# StLink.net
KiCad netlist of a schematic drawn in Altium Designer
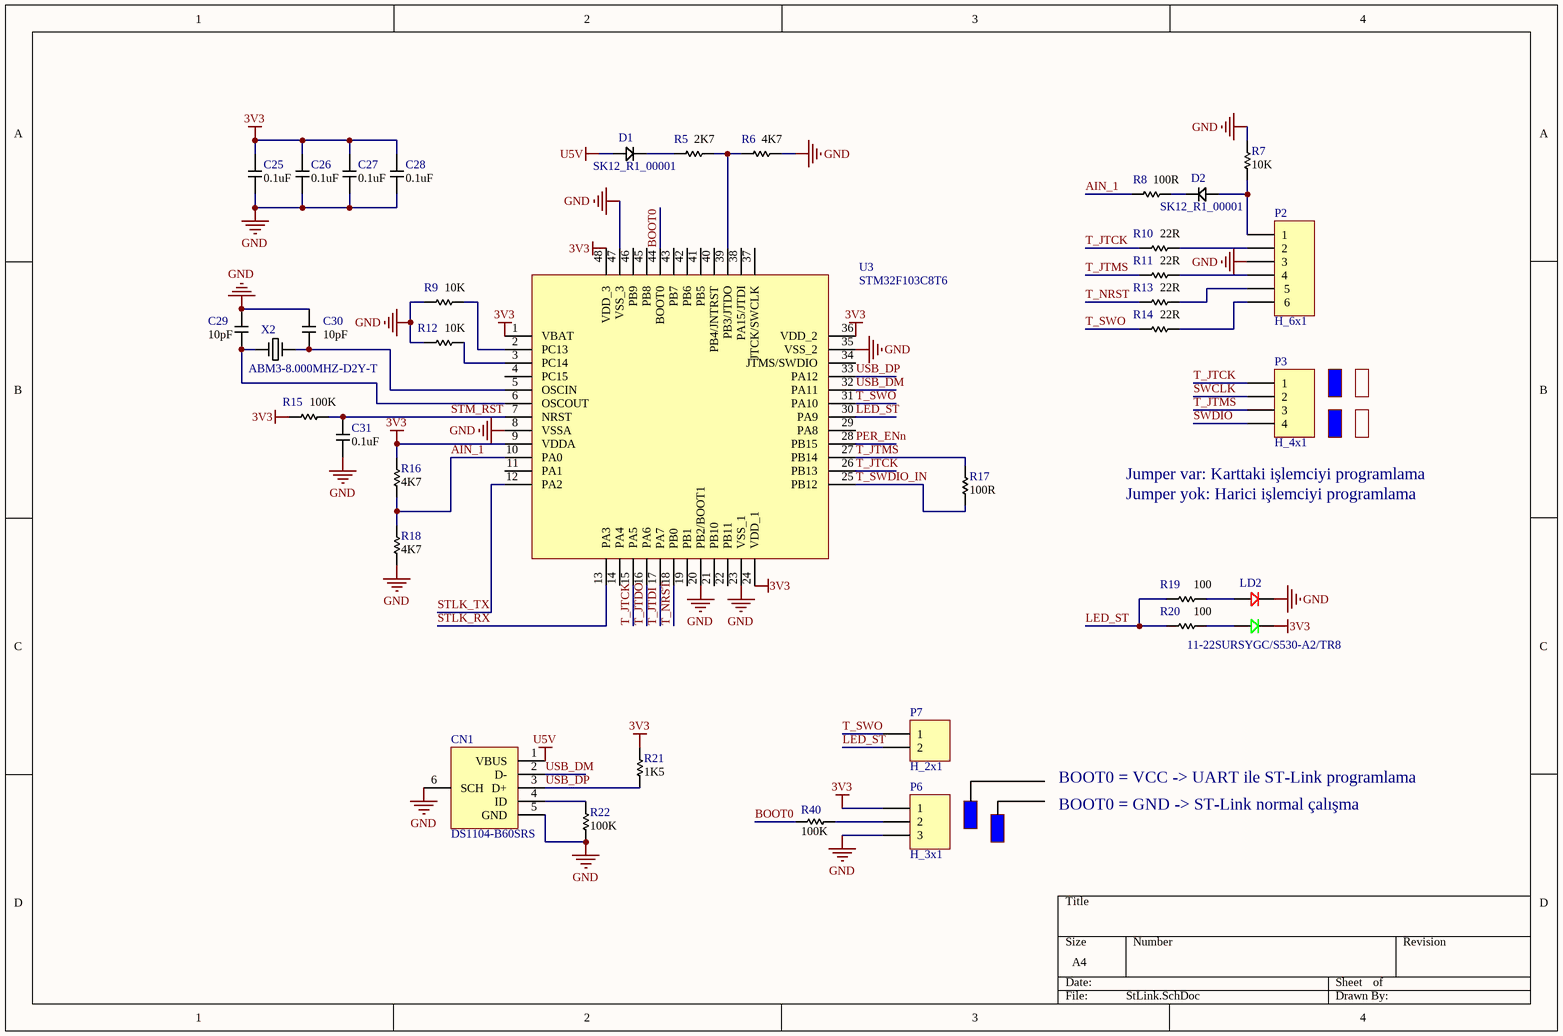
[diagram p0: StLink.SchDoc]

(export (version "E")
  (design (tool "Eeschema 10.0.6"))
  (components
    (comp (ref "C25")
      (value "0.1uF")
      (footprint "Kemet_0805_X7R")
      (description "Cap_0805_0.1uF_25VDC_Kemet")
      (fields (field (name "MANUFACTURER") "Kemet") (field (name "VOLTAGE") "25VDC"))
      (libsource (lib "Capacitor") (part "C0805C104K3RACTU"))
    )
    (comp (ref "C26")
      (value "0.1uF")
      (footprint "Kemet_0805_X7R")
      (description "Cap_0805_0.1uF_25VDC_Kemet")
      (fields (field (name "MANUFACTURER") "Kemet") (field (name "VOLTAGE") "25VDC"))
      (libsource (lib "Capacitor") (part "C0805C104K3RACTU"))
    )
    (comp (ref "C27")
      (value "0.1uF")
      (footprint "Kemet_0805_X7R")
      (description "Cap_0805_0.1uF_25VDC_Kemet")
      (fields (field (name "MANUFACTURER") "Kemet") (field (name "VOLTAGE") "25VDC"))
      (libsource (lib "Capacitor") (part "C0805C104K3RACTU"))
    )
    (comp (ref "C28")
      (value "0.1uF")
      (footprint "Kemet_0805_X7R")
      (description "Cap_0805_0.1uF_25VDC_Kemet")
      (fields (field (name "MANUFACTURER") "Kemet") (field (name "VOLTAGE") "25VDC"))
      (libsource (lib "Capacitor") (part "C0805C104K3RACTU"))
    )
    (comp (ref "C29")
      (value "10pF")
      (footprint "Kemet_0805_X7R")
      (description "Cap_0805_0.1uF_25VDC_Kemet")
      (fields (field (name "MANUFACTURER") "Kemet") (field (name "VOLTAGE") "25VDC"))
      (libsource (lib "Capacitor") (part "C0805C104K3RACTU"))
    )
    (comp (ref "C30")
      (value "10pF")
      (footprint "Kemet_0805_X7R")
      (description "Cap_0805_0.1uF_25VDC_Kemet")
      (fields (field (name "MANUFACTURER") "Kemet") (field (name "VOLTAGE") "25VDC"))
      (libsource (lib "Capacitor") (part "C0805C104K3RACTU"))
    )
    (comp (ref "C31")
      (value "0.1uF")
      (footprint "Kemet_0805_X7R")
      (description "Cap_0805_0.1uF_25VDC_Kemet")
      (fields (field (name "MANUFACTURER") "Kemet") (field (name "VOLTAGE") "25VDC"))
      (libsource (lib "Capacitor") (part "C0805C104K3RACTU"))
    )
    (comp (ref "CN1")
      (value "DS1104-B60SRS")
      (footprint "Connfly_DS1104-B60SRS")
      (description "UsbConn_Mini_5Pin_SMT_Connfly")
      (libsource (lib "UsbConnecttor") (part "DS1104-B60SRS"))
    )
    (comp (ref "D1")
      (value "SK12_R1_00001")
      (footprint "Panjit_DO214AA_2")
      (description "Schottky_1A_0.6V_20V_Panjit")
      (fields (field (name "MANUFACTURER") "Panjit"))
      (libsource (lib "Diode") (part "SK12_R1_00001"))
    )
    (comp (ref "D2")
      (value "SK12_R1_00001")
      (footprint "Panjit_DO214AA_2")
      (description "Schottky_1A_0.6V_20V_Panjit")
      (fields (field (name "MANUFACTURER") "Panjit"))
      (libsource (lib "Diode") (part "SK12_R1_00001"))
    )
    (comp (ref "LD2")
      (value "11-22SURSYGC/S530-A2/TR8")
      (footprint "Everlight_11-22SURSYGC")
      (description "Led_RG_1.7-2.4V_25mA_Everlight")
      (fields (field (name "MANUFACTURER") "Everlight"))
      (libsource (lib "LED") (part "11-22SURSYGC/S530-A2/TR8"))
    )
    (comp (ref "P2")
      (value "H_6x1")
      (footprint "HEADER_HDRV6W65P254_6X1_1524X254H945")
      (description "Head_6x1_2.54")
      (libsource (lib "Header") (part "H_6x1"))
    )
    (comp (ref "P3")
      (value "H_4x1")
      (footprint "HEADER_HDRV4W65P254_4X1_1016X254H945")
      (description "Head_4x1_2.54")
      (libsource (lib "Header") (part "H_4x1"))
    )
    (comp (ref "P6")
      (value "H_3x1")
      (footprint "HEADER_HDRV3W65P254_3X1_762X254H945")
      (description "Head_3x1_2.54")
      (libsource (lib "Header") (part "H_3x1"))
    )
    (comp (ref "P7")
      (value "H_2x1")
      (footprint "HEADER_HDRV2W65P254_2X1_508X254H945")
      (description "Head_2x1_2.54")
      (libsource (lib "Header") (part "H_2x1"))
    )
    (comp (ref "R5")
      (value "2K7")
      (footprint "VISHAY_RESC205X125X50L35_30N")
      (description "Res_0805_0R_1/8W_Vishay")
      (fields (field (name "MANUFACTURER") "Vishay") (field (name "POWER") "1/8W"))
      (libsource (lib "Resistor") (part "CRCW08050000Z0EA"))
    )
    (comp (ref "R6")
      (value "4K7")
      (footprint "VISHAY_RESC205X125X50L35_30N")
      (description "Res_0805_0R_1/8W_Vishay")
      (fields (field (name "MANUFACTURER") "Vishay") (field (name "POWER") "1/8W"))
      (libsource (lib "Resistor") (part "CRCW08050000Z0EA"))
    )
    (comp (ref "R7")
      (value "10K")
      (footprint "VISHAY_RESC205X125X50L35_30N")
      (description "Res_0805_0R_1/8W_Vishay")
      (fields (field (name "MANUFACTURER") "Vishay") (field (name "POWER") "1/8W"))
      (libsource (lib "Resistor") (part "CRCW08050000Z0EA"))
    )
    (comp (ref "R8")
      (value "100R")
      (footprint "VISHAY_RESC205X125X50L35_30N")
      (description "Res_0805_0R_1/8W_Vishay")
      (fields (field (name "MANUFACTURER") "Vishay") (field (name "POWER") "1/8W"))
      (libsource (lib "Resistor") (part "CRCW08050000Z0EA"))
    )
    (comp (ref "R9")
      (value "10K")
      (footprint "VISHAY_RESC205X125X50L35_30N")
      (description "Res_0805_0R_1/8W_Vishay")
      (fields (field (name "MANUFACTURER") "Vishay") (field (name "POWER") "1/8W"))
      (libsource (lib "Resistor") (part "CRCW08050000Z0EA"))
    )
    (comp (ref "R10")
      (value "22R")
      (footprint "VISHAY_RESC205X125X50L35_30N")
      (description "Res_0805_0R_1/8W_Vishay")
      (fields (field (name "MANUFACTURER") "Vishay") (field (name "POWER") "1/8W"))
      (libsource (lib "Resistor") (part "CRCW08050000Z0EA"))
    )
    (comp (ref "R11")
      (value "22R")
      (footprint "VISHAY_RESC205X125X50L35_30N")
      (description "Res_0805_0R_1/8W_Vishay")
      (fields (field (name "MANUFACTURER") "Vishay") (field (name "POWER") "1/8W"))
      (libsource (lib "Resistor") (part "CRCW08050000Z0EA"))
    )
    (comp (ref "R12")
      (value "10K")
      (footprint "VISHAY_RESC205X125X50L35_30N")
      (description "Res_0805_0R_1/8W_Vishay")
      (fields (field (name "MANUFACTURER") "Vishay") (field (name "POWER") "1/8W"))
      (libsource (lib "Resistor") (part "CRCW08050000Z0EA"))
    )
    (comp (ref "R13")
      (value "22R")
      (footprint "VISHAY_RESC205X125X50L35_30N")
      (description "Res_0805_0R_1/8W_Vishay")
      (fields (field (name "MANUFACTURER") "Vishay") (field (name "POWER") "1/8W"))
      (libsource (lib "Resistor") (part "CRCW08050000Z0EA"))
    )
    (comp (ref "R14")
      (value "22R")
      (footprint "VISHAY_RESC205X125X50L35_30N")
      (description "Res_0805_0R_1/8W_Vishay")
      (fields (field (name "MANUFACTURER") "Vishay") (field (name "POWER") "1/8W"))
      (libsource (lib "Resistor") (part "CRCW08050000Z0EA"))
    )
    (comp (ref "R15")
      (value "100K")
      (footprint "VISHAY_RESC205X125X50L35_30N")
      (description "Res_0805_0R_1/8W_Vishay")
      (fields (field (name "MANUFACTURER") "Vishay") (field (name "POWER") "1/8W"))
      (libsource (lib "Resistor") (part "CRCW08050000Z0EA"))
    )
    (comp (ref "R16")
      (value "4K7")
      (footprint "VISHAY_RESC205X125X50L35_30N")
      (description "Res_0805_0R_1/8W_Vishay")
      (fields (field (name "MANUFACTURER") "Vishay") (field (name "POWER") "1/8W"))
      (libsource (lib "Resistor") (part "CRCW08050000Z0EA"))
    )
    (comp (ref "R17")
      (value "100R")
      (footprint "VISHAY_RESC205X125X50L35_30N")
      (description "Res_0805_0R_1/8W_Vishay")
      (fields (field (name "MANUFACTURER") "Vishay") (field (name "POWER") "1/8W"))
      (libsource (lib "Resistor") (part "CRCW08050000Z0EA"))
    )
    (comp (ref "R18")
      (value "4K7")
      (footprint "VISHAY_RESC205X125X50L35_30N")
      (description "Res_0805_0R_1/8W_Vishay")
      (fields (field (name "MANUFACTURER") "Vishay") (field (name "POWER") "1/8W"))
      (libsource (lib "Resistor") (part "CRCW08050000Z0EA"))
    )
    (comp (ref "R19")
      (value "100")
      (footprint "VISHAY_RESC205X125X50L35_30N")
      (description "Res_0805_0R_1/8W_Vishay")
      (fields (field (name "MANUFACTURER") "Vishay") (field (name "POWER") "1/8W"))
      (libsource (lib "Resistor") (part "CRCW08050000Z0EA"))
    )
    (comp (ref "R20")
      (value "100")
      (footprint "VISHAY_RESC205X125X50L35_30N")
      (description "Res_0805_0R_1/8W_Vishay")
      (fields (field (name "MANUFACTURER") "Vishay") (field (name "POWER") "1/8W"))
      (libsource (lib "Resistor") (part "CRCW08050000Z0EA"))
    )
    (comp (ref "R21")
      (value "1K5")
      (footprint "VISHAY_RESC205X125X50L35_30N")
      (description "Res_0805_0R_1/8W_Vishay")
      (fields (field (name "MANUFACTURER") "Vishay") (field (name "POWER") "1/8W"))
      (libsource (lib "Resistor") (part "CRCW08050000Z0EA"))
    )
    (comp (ref "R22")
      (value "100K")
      (footprint "VISHAY_RESC205X125X50L35_30N")
      (description "Res_0805_0R_1/8W_Vishay")
      (fields (field (name "MANUFACTURER") "Vishay") (field (name "POWER") "1/8W"))
      (libsource (lib "Resistor") (part "CRCW08050000Z0EA"))
    )
    (comp (ref "R40")
      (value "100K")
      (footprint "VISHAY_RESC205X125X50L35_30N")
      (description "Res_0805_0R_1/8W_Vishay")
      (fields (field (name "MANUFACTURER") "Vishay") (field (name "POWER") "1/8W"))
      (libsource (lib "Resistor") (part "CRCW08050000Z0EA"))
    )
    (comp (ref "U3")
      (value "STM32F103C8T6")
      (footprint "STM_QFP48P50_900X900X160L60X22N")
      (description "Microcontroller_STM")
      (fields (field (name "MANUFACTURER") "STM"))
      (libsource (lib "Microcontroller") (part "STM32F103C8T6"))
    )
    (comp (ref "X2")
      (value "ABM3-8.000MHZ-D2Y-T")
      (footprint "ABRACON_XTALDFN2_500X320X130L130X200N")
      (description "Crystal_8MHz_18pF_140R_20PPM_30PPM_Abracon")
      (fields (field (name "MANUFACTURER") "Abracon"))
      (libsource (lib "Crystal") (part "ABM3-8.000MHZ-D2Y-T"))
    )
  )
  (nets
    (net (code "1") (name "/AIN_1") (class "Default")
      (node (ref "R16") (pin "1") (pinfunction "1_1") (pintype "passive"))
      (node (ref "R18") (pin "2") (pinfunction "2_2") (pintype "passive"))
      (node (ref "R8") (pin "2") (pinfunction "2_2") (pintype "passive"))
      (node (ref "U3") (pin "10") (pinfunction "PA0_10") (pintype "passive"))
    )
    (net (code "2") (name "/BOOT0") (class "Default")
      (node (ref "R40") (pin "2") (pinfunction "2_2") (pintype "passive"))
      (node (ref "U3") (pin "44") (pinfunction "BOOT0_44") (pintype "passive"))
    )
    (net (code "3") (name "/LED_ST") (class "Default")
      (node (ref "P7") (pin "2") (pinfunction "2_2") (pintype "passive"))
      (node (ref "R19") (pin "2") (pinfunction "2_2") (pintype "passive"))
      (node (ref "R20") (pin "2") (pinfunction "2_2") (pintype "passive"))
      (node (ref "U3") (pin "30") (pinfunction "PA9_30") (pintype "passive"))
    )
    (net (code "4") (name "/PER_ENn") (class "Default")
      (node (ref "U3") (pin "28") (pinfunction "PB15_28") (pintype "passive"))
    )
    (net (code "5") (name "/STLK_RX") (class "Default")
      (node (ref "U3") (pin "13") (pinfunction "PA3_13") (pintype "passive"))
    )
    (net (code "6") (name "/STLK_TX") (class "Default")
      (node (ref "U3") (pin "12") (pinfunction "PA2_12") (pintype "passive"))
    )
    (net (code "7") (name "/STM_RST") (class "Default")
      (node (ref "C31") (pin "2") (pinfunction "2_2") (pintype "passive"))
      (node (ref "R15") (pin "2") (pinfunction "2_2") (pintype "passive"))
      (node (ref "U3") (pin "7") (pinfunction "NRST_7") (pintype "passive"))
    )
    (net (code "8") (name "/SWCLK") (class "Default")
      (node (ref "P3") (pin "2") (pinfunction "2_2") (pintype "passive"))
    )
    (net (code "9") (name "/SWDIO") (class "Default")
      (node (ref "P3") (pin "4") (pinfunction "4_4") (pintype "passive"))
    )
    (net (code "10") (name "/T_JTCK") (class "Default")
      (node (ref "P3") (pin "1") (pinfunction "1_1") (pintype "passive"))
      (node (ref "R10") (pin "2") (pinfunction "2_2") (pintype "passive"))
      (node (ref "U3") (pin "15") (pinfunction "PA5_15") (pintype "passive"))
      (node (ref "U3") (pin "26") (pinfunction "PB13_26") (pintype "passive"))
    )
    (net (code "11") (name "/T_JTDI") (class "Default")
      (node (ref "U3") (pin "17") (pinfunction "PA7_17") (pintype "passive"))
    )
    (net (code "12") (name "/T_JTDO") (class "Default")
      (node (ref "U3") (pin "16") (pinfunction "PA6_16") (pintype "passive"))
    )
    (net (code "13") (name "/T_JTMS") (class "Default")
      (node (ref "P3") (pin "3") (pinfunction "3_3") (pintype "passive"))
      (node (ref "R11") (pin "2") (pinfunction "2_2") (pintype "passive"))
      (node (ref "R17") (pin "1") (pinfunction "1_1") (pintype "passive"))
      (node (ref "U3") (pin "27") (pinfunction "PB14_27") (pintype "passive"))
    )
    (net (code "14") (name "/T_NRST") (class "Default")
      (node (ref "R13") (pin "2") (pinfunction "2_2") (pintype "passive"))
      (node (ref "U3") (pin "18") (pinfunction "PB0_18") (pintype "passive"))
    )
    (net (code "15") (name "/T_SWDIO_IN") (class "Default")
      (node (ref "R17") (pin "2") (pinfunction "2_2") (pintype "passive"))
      (node (ref "U3") (pin "25") (pinfunction "PB12_25") (pintype "passive"))
    )
    (net (code "16") (name "/T_SWO") (class "Default")
      (node (ref "P7") (pin "1") (pinfunction "1_1") (pintype "passive"))
      (node (ref "R14") (pin "2") (pinfunction "2_2") (pintype "passive"))
      (node (ref "U3") (pin "31") (pinfunction "PA10_31") (pintype "passive"))
    )
    (net (code "17") (name "/USB_DM") (class "Default")
      (node (ref "CN1") (pin "2") (pinfunction "D-_2") (pintype "passive"))
      (node (ref "U3") (pin "32") (pinfunction "PA11_32") (pintype "passive"))
    )
    (net (code "18") (name "/USB_DP") (class "Default")
      (node (ref "CN1") (pin "3") (pinfunction "D+_3") (pintype "passive"))
      (node (ref "R21") (pin "1") (pinfunction "1_1") (pintype "passive"))
      (node (ref "U3") (pin "33") (pinfunction "PA12_33") (pintype "passive"))
    )
    (net (code "19") (name "3V3") (class "Default")
      (node (ref "C25") (pin "2") (pinfunction "2_2") (pintype "passive"))
      (node (ref "C26") (pin "2") (pinfunction "2_2") (pintype "passive"))
      (node (ref "C27") (pin "2") (pinfunction "2_2") (pintype "passive"))
      (node (ref "C28") (pin "2") (pinfunction "2_2") (pintype "passive"))
      (node (ref "LD2") (pin "4") (pinfunction "G-_4") (pintype "passive"))
      (node (ref "P6") (pin "1") (pinfunction "1_1") (pintype "passive"))
      (node (ref "R15") (pin "1") (pinfunction "1_1") (pintype "passive"))
      (node (ref "R16") (pin "2") (pinfunction "2_2") (pintype "passive"))
      (node (ref "R21") (pin "2") (pinfunction "2_2") (pintype "passive"))
      (node (ref "U3") (pin "1") (pinfunction "VBAT_1") (pintype "passive"))
      (node (ref "U3") (pin "24") (pinfunction "VDD_1_24") (pintype "passive"))
      (node (ref "U3") (pin "36") (pinfunction "VDD_2_36") (pintype "passive"))
      (node (ref "U3") (pin "48") (pinfunction "VDD_3_48") (pintype "passive"))
      (node (ref "U3") (pin "9") (pinfunction "VDDA_9") (pintype "passive"))
    )
    (net (code "20") (name "GND") (class "Default")
      (node (ref "C25") (pin "1") (pinfunction "1_1") (pintype "passive"))
      (node (ref "C26") (pin "1") (pinfunction "1_1") (pintype "passive"))
      (node (ref "C27") (pin "1") (pinfunction "1_1") (pintype "passive"))
      (node (ref "C28") (pin "1") (pinfunction "1_1") (pintype "passive"))
      (node (ref "C29") (pin "2") (pinfunction "2_2") (pintype "passive"))
      (node (ref "C30") (pin "2") (pinfunction "2_2") (pintype "passive"))
      (node (ref "C31") (pin "1") (pinfunction "1_1") (pintype "passive"))
      (node (ref "CN1") (pin "5") (pinfunction "GND_5") (pintype "passive"))
      (node (ref "CN1") (pin "6") (pinfunction "SCH_6") (pintype "passive"))
      (node (ref "LD2") (pin "2") (pinfunction "R-_2") (pintype "passive"))
      (node (ref "P2") (pin "3") (pinfunction "3_3") (pintype "passive"))
      (node (ref "P6") (pin "3") (pinfunction "3_3") (pintype "passive"))
      (node (ref "R12") (pin "1") (pinfunction "1_1") (pintype "passive"))
      (node (ref "R18") (pin "1") (pinfunction "1_1") (pintype "passive"))
      (node (ref "R22") (pin "2") (pinfunction "2_2") (pintype "passive"))
      (node (ref "R6") (pin "2") (pinfunction "2_2") (pintype "passive"))
      (node (ref "R7") (pin "2") (pinfunction "2_2") (pintype "passive"))
      (node (ref "R9") (pin "1") (pinfunction "1_1") (pintype "passive"))
      (node (ref "U3") (pin "20") (pinfunction "PB2/BOOT1_20") (pintype "passive"))
      (node (ref "U3") (pin "23") (pinfunction "VSS_1_23") (pintype "passive"))
      (node (ref "U3") (pin "35") (pinfunction "VSS_2_35") (pintype "passive"))
      (node (ref "U3") (pin "47") (pinfunction "VSS_3_47") (pintype "passive"))
      (node (ref "U3") (pin "8") (pinfunction "VSSA_8") (pintype "passive"))
    )
    (net (code "21") (name "Net-(CN1-ID)") (class "Default")
      (node (ref "CN1") (pin "4") (pinfunction "ID_4") (pintype "passive"))
      (node (ref "R22") (pin "1") (pinfunction "1_1") (pintype "passive"))
    )
    (net (code "22") (name "Net-(D1-C)") (class "Default")
      (node (ref "D1") (pin "2") (pinfunction "C_2") (pintype "passive"))
      (node (ref "R5") (pin "1") (pinfunction "1_1") (pintype "passive"))
    )
    (net (code "23") (name "Net-(D2-A)") (class "Default")
      (node (ref "D2") (pin "1") (pinfunction "A_1") (pintype "passive"))
      (node (ref "P2") (pin "1") (pinfunction "1_1") (pintype "passive"))
      (node (ref "R7") (pin "1") (pinfunction "1_1") (pintype "passive"))
    )
    (net (code "24") (name "Net-(D2-C)") (class "Default")
      (node (ref "D2") (pin "2") (pinfunction "C_2") (pintype "passive"))
      (node (ref "R8") (pin "1") (pinfunction "1_1") (pintype "passive"))
    )
    (net (code "25") (name "Net-(LD2-G+)") (class "Default")
      (node (ref "LD2") (pin "3") (pinfunction "G+_3") (pintype "passive"))
      (node (ref "R20") (pin "1") (pinfunction "1_1") (pintype "passive"))
    )
    (net (code "26") (name "Net-(LD2-R+)") (class "Default")
      (node (ref "LD2") (pin "1") (pinfunction "R+_1") (pintype "passive"))
      (node (ref "R19") (pin "1") (pinfunction "1_1") (pintype "passive"))
    )
    (net (code "27") (name "Net-(P2-Pad2)") (class "Default")
      (node (ref "P2") (pin "2") (pinfunction "2_2") (pintype "passive"))
      (node (ref "R10") (pin "1") (pinfunction "1_1") (pintype "passive"))
    )
    (net (code "28") (name "Net-(P2-Pad4)") (class "Default")
      (node (ref "P2") (pin "4") (pinfunction "4_4") (pintype "passive"))
      (node (ref "R11") (pin "1") (pinfunction "1_1") (pintype "passive"))
    )
    (net (code "29") (name "Net-(P2-Pad5)") (class "Default")
      (node (ref "P2") (pin "5") (pinfunction "5_5") (pintype "passive"))
      (node (ref "R13") (pin "1") (pinfunction "1_1") (pintype "passive"))
    )
    (net (code "30") (name "Net-(P2-Pad6)") (class "Default")
      (node (ref "P2") (pin "6") (pinfunction "6_6") (pintype "passive"))
      (node (ref "R14") (pin "1") (pinfunction "1_1") (pintype "passive"))
    )
    (net (code "31") (name "Net-(P6-Pad2)") (class "Default")
      (node (ref "P6") (pin "2") (pinfunction "2_2") (pintype "passive"))
      (node (ref "R40") (pin "1") (pinfunction "1_1") (pintype "passive"))
    )
    (net (code "32") (name "Net-(U3-OSCIN)") (class "Default")
      (node (ref "C30") (pin "1") (pinfunction "1_1") (pintype "passive"))
      (node (ref "U3") (pin "5") (pinfunction "OSCIN_5") (pintype "passive"))
      (node (ref "X2") (pin "2") (pinfunction "2_2") (pintype "passive"))
    )
    (net (code "33") (name "Net-(U3-OSCOUT)") (class "Default")
      (node (ref "C29") (pin "1") (pinfunction "1_1") (pintype "passive"))
      (node (ref "U3") (pin "6") (pinfunction "OSCOUT_6") (pintype "passive"))
      (node (ref "X2") (pin "1") (pinfunction "1_1") (pintype "passive"))
    )
    (net (code "34") (name "Net-(U3-PB3{slash}JTDO)") (class "Default")
      (node (ref "R5") (pin "2") (pinfunction "2_2") (pintype "passive"))
      (node (ref "R6") (pin "1") (pinfunction "1_1") (pintype "passive"))
      (node (ref "U3") (pin "39") (pinfunction "PB3/JTDO_39") (pintype "passive"))
    )
    (net (code "35") (name "Net-(U3-PC13)") (class "Default")
      (node (ref "R9") (pin "2") (pinfunction "2_2") (pintype "passive"))
      (node (ref "U3") (pin "2") (pinfunction "PC13_2") (pintype "passive"))
    )
    (net (code "36") (name "Net-(U3-PC14)") (class "Default")
      (node (ref "R12") (pin "2") (pinfunction "2_2") (pintype "passive"))
      (node (ref "U3") (pin "3") (pinfunction "PC14_3") (pintype "passive"))
    )
    (net (code "37") (name "U5V") (class "Default")
      (node (ref "CN1") (pin "1") (pinfunction "VBUS_1") (pintype "passive"))
      (node (ref "D1") (pin "1") (pinfunction "A_1") (pintype "passive"))
    )
    (net (code "38") (name "unconnected-(U3-JTCK{slash}SWCLK-Pad37)") (class "Default")
      (node (ref "U3") (pin "37") (pinfunction "JTCK/SWCLK_37") (pintype "passive"))
    )
    (net (code "39") (name "unconnected-(U3-JTMS{slash}SWDIO-Pad34)") (class "Default")
      (node (ref "U3") (pin "34") (pinfunction "JTMS/SWDIO_34") (pintype "passive"))
    )
    (net (code "40") (name "unconnected-(U3-PA1-Pad11)") (class "Default")
      (node (ref "U3") (pin "11") (pinfunction "PA1_11") (pintype "passive"))
    )
    (net (code "41") (name "unconnected-(U3-PA4-Pad14)") (class "Default")
      (node (ref "U3") (pin "14") (pinfunction "PA4_14") (pintype "passive"))
    )
    (net (code "42") (name "unconnected-(U3-PA8-Pad29)") (class "Default")
      (node (ref "U3") (pin "29") (pinfunction "PA8_29") (pintype "passive"))
    )
    (net (code "43") (name "unconnected-(U3-PA15{slash}JTDI-Pad38)") (class "Default")
      (node (ref "U3") (pin "38") (pinfunction "PA15/JTDI_38") (pintype "passive"))
    )
    (net (code "44") (name "unconnected-(U3-PB1-Pad19)") (class "Default")
      (node (ref "U3") (pin "19") (pinfunction "PB1_19") (pintype "passive"))
    )
    (net (code "45") (name "unconnected-(U3-PB4{slash}JNTRST-Pad40)") (class "Default")
      (node (ref "U3") (pin "40") (pinfunction "PB4/JNTRST_40") (pintype "passive"))
    )
    (net (code "46") (name "unconnected-(U3-PB5-Pad41)") (class "Default")
      (node (ref "U3") (pin "41") (pinfunction "PB5_41") (pintype "passive"))
    )
    (net (code "47") (name "unconnected-(U3-PB6-Pad42)") (class "Default")
      (node (ref "U3") (pin "42") (pinfunction "PB6_42") (pintype "passive"))
    )
    (net (code "48") (name "unconnected-(U3-PB7-Pad43)") (class "Default")
      (node (ref "U3") (pin "43") (pinfunction "PB7_43") (pintype "passive"))
    )
    (net (code "49") (name "unconnected-(U3-PB8-Pad45)") (class "Default")
      (node (ref "U3") (pin "45") (pinfunction "PB8_45") (pintype "passive"))
    )
    (net (code "50") (name "unconnected-(U3-PB9-Pad46)") (class "Default")
      (node (ref "U3") (pin "46") (pinfunction "PB9_46") (pintype "passive"))
    )
    (net (code "51") (name "unconnected-(U3-PB10-Pad21)") (class "Default")
      (node (ref "U3") (pin "21") (pinfunction "PB10_21") (pintype "passive"))
    )
    (net (code "52") (name "unconnected-(U3-PB11-Pad22)") (class "Default")
      (node (ref "U3") (pin "22") (pinfunction "PB11_22") (pintype "passive"))
    )
    (net (code "53") (name "unconnected-(U3-PC15-Pad4)") (class "Default")
      (node (ref "U3") (pin "4") (pinfunction "PC15_4") (pintype "passive"))
    )
  )
)
